# 2026-06-01_v1_0_2.net
KiCad netlist of a schematic drawn in EasyEDA Pro
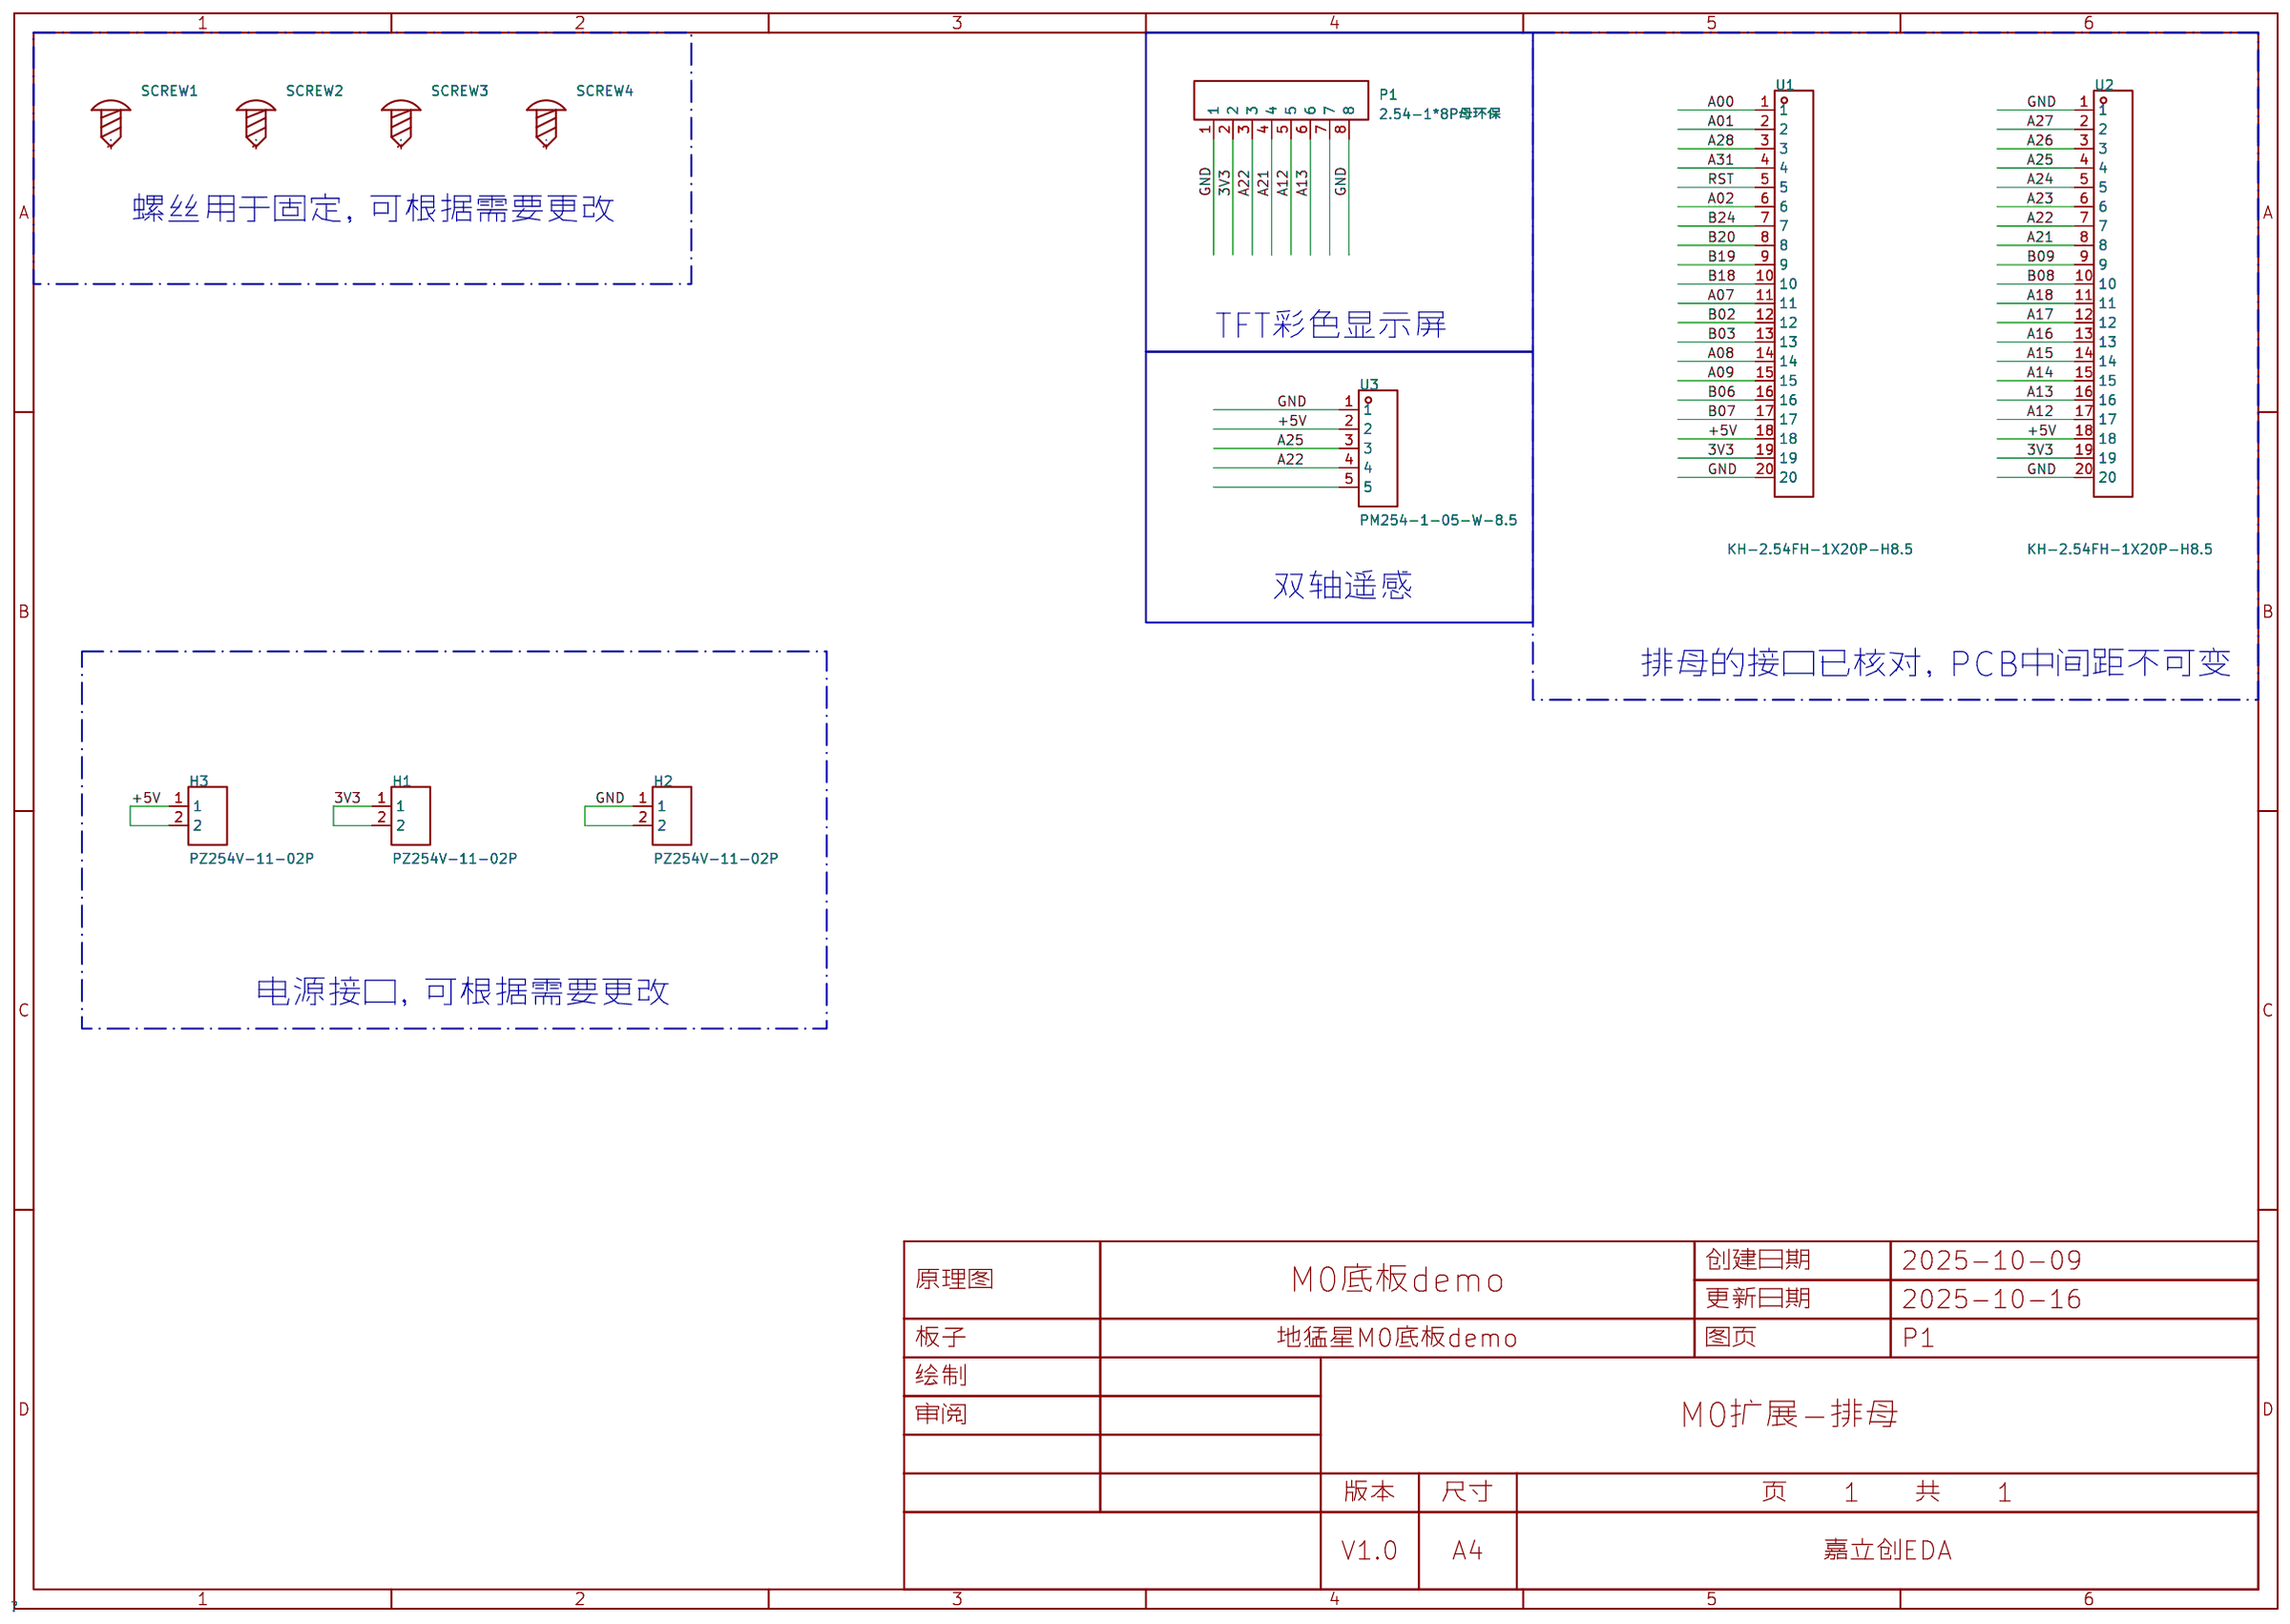
[diagram p0: schematic sheet]

(export (version "E")
  (design (tool "Eeschema 10.0.6"))
  (components
    (comp (ref "H1")
      (value "PZ254V-11-02P")
      (footprint "easyedapro:HDR-TH_2P-P2.54-V-M")
      (fields (field (name "Manufacturer") "XFCN(兴飞)"))
      (libsource (lib "easyedapro") (part "PZ254V-11-02P"))
    )
    (comp (ref "H2")
      (value "PZ254V-11-02P")
      (footprint "easyedapro:HDR-TH_2P-P2.54-V-M")
      (fields (field (name "Manufacturer") "XFCN(兴飞)"))
      (libsource (lib "easyedapro") (part "PZ254V-11-02P"))
    )
    (comp (ref "H3")
      (value "PZ254V-11-02P")
      (footprint "easyedapro:HDR-TH_2P-P2.54-V-M")
      (fields (field (name "Manufacturer") "XFCN(兴飞)"))
      (libsource (lib "easyedapro") (part "PZ254V-11-02P"))
    )
    (comp (ref "P1")
      (value "2.54-1*8P母环保")
      (footprint "easyedapro:HDR-TH_8P-P2.54-V-F")
      (fields (field (name "Manufacturer") "BOOMELE(博穆精密)"))
      (libsource (lib "easyedapro") (part "Header-Female-2.54_1x8"))
    )
    (comp (ref "SCREW1")
      (value "~")
      (footprint "easyedapro:M3螺丝")
      (libsource (lib "easyedapro") (part "螺丝孔"))
    )
    (comp (ref "SCREW2")
      (value "~")
      (footprint "easyedapro:M3螺丝")
      (libsource (lib "easyedapro") (part "螺丝孔"))
    )
    (comp (ref "SCREW3")
      (value "~")
      (footprint "easyedapro:M3螺丝")
      (libsource (lib "easyedapro") (part "螺丝孔"))
    )
    (comp (ref "SCREW4")
      (value "~")
      (footprint "easyedapro:M3螺丝")
      (libsource (lib "easyedapro") (part "螺丝孔"))
    )
    (comp (ref "U1")
      (value "KH-2.54FH-1X20P-H8.5")
      (footprint "easyedapro:HDR-TH_20P-P2.54-V-F-2")
      (fields (field (name "Manufacturer") "kinghelm(金航标)"))
      (libsource (lib "easyedapro") (part "KH-2.54FH-1X20P-H8.5"))
    )
    (comp (ref "U2")
      (value "KH-2.54FH-1X20P-H8.5")
      (footprint "easyedapro:HDR-TH_20P-P2.54-V-F-2")
      (fields (field (name "Manufacturer") "kinghelm(金航标)"))
      (libsource (lib "easyedapro") (part "KH-2.54FH-1X20P-H8.5"))
    )
    (comp (ref "U3")
      (value "PM254-1-05-W-8.5")
      (footprint "easyedapro:HDR-TH_5P-P2.54-H-F-W10.0-N")
      (fields (field (name "Manufacturer") "HCTL(华灿天禄)"))
      (libsource (lib "easyedapro") (part "PM254-1-05-W-8.5"))
    )
  )
  (nets
    (net (code "1") (name "/+5V") (class "Default")
      (node (ref "H3") (pin "1") (pinfunction "1_1") (pintype "unspecified"))
      (node (ref "H3") (pin "2") (pinfunction "2_2") (pintype "unspecified"))
      (node (ref "U1") (pin "18") (pinfunction "18_18") (pintype "unspecified"))
      (node (ref "U2") (pin "18") (pinfunction "18_18") (pintype "unspecified"))
      (node (ref "U3") (pin "2") (pinfunction "2_2") (pintype "unspecified"))
    )
    (net (code "2") (name "/3V3") (class "Default")
      (node (ref "H1") (pin "1") (pinfunction "1_1") (pintype "unspecified"))
      (node (ref "H1") (pin "2") (pinfunction "2_2") (pintype "unspecified"))
      (node (ref "P1") (pin "2") (pinfunction "2_2") (pintype "unspecified"))
      (node (ref "U1") (pin "19") (pinfunction "19_19") (pintype "unspecified"))
      (node (ref "U2") (pin "19") (pinfunction "19_19") (pintype "unspecified"))
    )
    (net (code "3") (name "/A00") (class "Default")
      (node (ref "U1") (pin "1") (pinfunction "1_1") (pintype "unspecified"))
    )
    (net (code "4") (name "/A01") (class "Default")
      (node (ref "U1") (pin "2") (pinfunction "2_2") (pintype "unspecified"))
    )
    (net (code "5") (name "/A02") (class "Default")
      (node (ref "U1") (pin "6") (pinfunction "6_6") (pintype "unspecified"))
    )
    (net (code "6") (name "/A07") (class "Default")
      (node (ref "U1") (pin "11") (pinfunction "11_11") (pintype "unspecified"))
    )
    (net (code "7") (name "/A08") (class "Default")
      (node (ref "U1") (pin "14") (pinfunction "14_14") (pintype "unspecified"))
    )
    (net (code "8") (name "/A09") (class "Default")
      (node (ref "U1") (pin "15") (pinfunction "15_15") (pintype "unspecified"))
    )
    (net (code "9") (name "/A12") (class "Default")
      (node (ref "P1") (pin "5") (pinfunction "5_5") (pintype "unspecified"))
      (node (ref "U2") (pin "17") (pinfunction "17_17") (pintype "unspecified"))
    )
    (net (code "10") (name "/A13") (class "Default")
      (node (ref "P1") (pin "6") (pinfunction "6_6") (pintype "unspecified"))
      (node (ref "U2") (pin "16") (pinfunction "16_16") (pintype "unspecified"))
    )
    (net (code "11") (name "/A14") (class "Default")
      (node (ref "U2") (pin "15") (pinfunction "15_15") (pintype "unspecified"))
    )
    (net (code "12") (name "/A15") (class "Default")
      (node (ref "U2") (pin "14") (pinfunction "14_14") (pintype "unspecified"))
    )
    (net (code "13") (name "/A16") (class "Default")
      (node (ref "U2") (pin "13") (pinfunction "13_13") (pintype "unspecified"))
    )
    (net (code "14") (name "/A17") (class "Default")
      (node (ref "U2") (pin "12") (pinfunction "12_12") (pintype "unspecified"))
    )
    (net (code "15") (name "/A18") (class "Default")
      (node (ref "U2") (pin "11") (pinfunction "11_11") (pintype "unspecified"))
    )
    (net (code "16") (name "/A21") (class "Default")
      (node (ref "P1") (pin "4") (pinfunction "4_4") (pintype "unspecified"))
      (node (ref "U2") (pin "8") (pinfunction "8_8") (pintype "unspecified"))
    )
    (net (code "17") (name "/A22") (class "Default")
      (node (ref "P1") (pin "3") (pinfunction "3_3") (pintype "unspecified"))
      (node (ref "U2") (pin "7") (pinfunction "7_7") (pintype "unspecified"))
      (node (ref "U3") (pin "4") (pinfunction "4_4") (pintype "unspecified"))
    )
    (net (code "18") (name "/A23") (class "Default")
      (node (ref "U2") (pin "6") (pinfunction "6_6") (pintype "unspecified"))
    )
    (net (code "19") (name "/A24") (class "Default")
      (node (ref "U2") (pin "5") (pinfunction "5_5") (pintype "unspecified"))
    )
    (net (code "20") (name "/A25") (class "Default")
      (node (ref "U2") (pin "4") (pinfunction "4_4") (pintype "unspecified"))
      (node (ref "U3") (pin "3") (pinfunction "3_3") (pintype "unspecified"))
    )
    (net (code "21") (name "/A26") (class "Default")
      (node (ref "U2") (pin "3") (pinfunction "3_3") (pintype "unspecified"))
    )
    (net (code "22") (name "/A27") (class "Default")
      (node (ref "U2") (pin "2") (pinfunction "2_2") (pintype "unspecified"))
    )
    (net (code "23") (name "/A28") (class "Default")
      (node (ref "U1") (pin "3") (pinfunction "3_3") (pintype "unspecified"))
    )
    (net (code "24") (name "/A31") (class "Default")
      (node (ref "U1") (pin "4") (pinfunction "4_4") (pintype "unspecified"))
    )
    (net (code "25") (name "/B02") (class "Default")
      (node (ref "U1") (pin "12") (pinfunction "12_12") (pintype "unspecified"))
    )
    (net (code "26") (name "/B03") (class "Default")
      (node (ref "U1") (pin "13") (pinfunction "13_13") (pintype "unspecified"))
    )
    (net (code "27") (name "/B06") (class "Default")
      (node (ref "U1") (pin "16") (pinfunction "16_16") (pintype "unspecified"))
    )
    (net (code "28") (name "/B07") (class "Default")
      (node (ref "U1") (pin "17") (pinfunction "17_17") (pintype "unspecified"))
    )
    (net (code "29") (name "/B08") (class "Default")
      (node (ref "U2") (pin "10") (pinfunction "10_10") (pintype "unspecified"))
    )
    (net (code "30") (name "/B09") (class "Default")
      (node (ref "U2") (pin "9") (pinfunction "9_9") (pintype "unspecified"))
    )
    (net (code "31") (name "/B18") (class "Default")
      (node (ref "U1") (pin "10") (pinfunction "10_10") (pintype "unspecified"))
    )
    (net (code "32") (name "/B19") (class "Default")
      (node (ref "U1") (pin "9") (pinfunction "9_9") (pintype "unspecified"))
    )
    (net (code "33") (name "/B20") (class "Default")
      (node (ref "U1") (pin "8") (pinfunction "8_8") (pintype "unspecified"))
    )
    (net (code "34") (name "/B24") (class "Default")
      (node (ref "U1") (pin "7") (pinfunction "7_7") (pintype "unspecified"))
    )
    (net (code "35") (name "/GND") (class "Default")
      (node (ref "H2") (pin "1") (pinfunction "1_1") (pintype "unspecified"))
      (node (ref "H2") (pin "2") (pinfunction "2_2") (pintype "unspecified"))
      (node (ref "P1") (pin "1") (pinfunction "1_1") (pintype "unspecified"))
      (node (ref "P1") (pin "8") (pinfunction "8_8") (pintype "unspecified"))
      (node (ref "U1") (pin "20") (pinfunction "20_20") (pintype "unspecified"))
      (node (ref "U2") (pin "1") (pinfunction "1_1") (pintype "unspecified"))
      (node (ref "U2") (pin "20") (pinfunction "20_20") (pintype "unspecified"))
      (node (ref "U3") (pin "1") (pinfunction "1_1") (pintype "unspecified"))
    )
    (net (code "36") (name "/RST") (class "Default")
      (node (ref "U1") (pin "5") (pinfunction "5_5") (pintype "unspecified"))
    )
    (net (code "37") (name "unconnected-(P1-Pad7)") (class "Default")
      (node (ref "P1") (pin "7") (pinfunction "7_7") (pintype "unspecified"))
    )
    (net (code "38") (name "unconnected-(SCREW1-Pad1)") (class "Default")
      (node (ref "SCREW1") (pin "1") (pinfunction "1_1") (pintype "input"))
    )
    (net (code "39") (name "unconnected-(SCREW2-Pad1)") (class "Default")
      (node (ref "SCREW2") (pin "1") (pinfunction "1_1") (pintype "input"))
    )
    (net (code "40") (name "unconnected-(SCREW3-Pad1)") (class "Default")
      (node (ref "SCREW3") (pin "1") (pinfunction "1_1") (pintype "input"))
    )
    (net (code "41") (name "unconnected-(SCREW4-Pad1)") (class "Default")
      (node (ref "SCREW4") (pin "1") (pinfunction "1_1") (pintype "input"))
    )
    (net (code "42") (name "unconnected-(U3-Pad5)") (class "Default")
      (node (ref "U3") (pin "5") (pinfunction "5_5") (pintype "unspecified"))
    )
  )
)
